# Power_Supply.net
KiCad netlist of a schematic drawn in Altium Designer
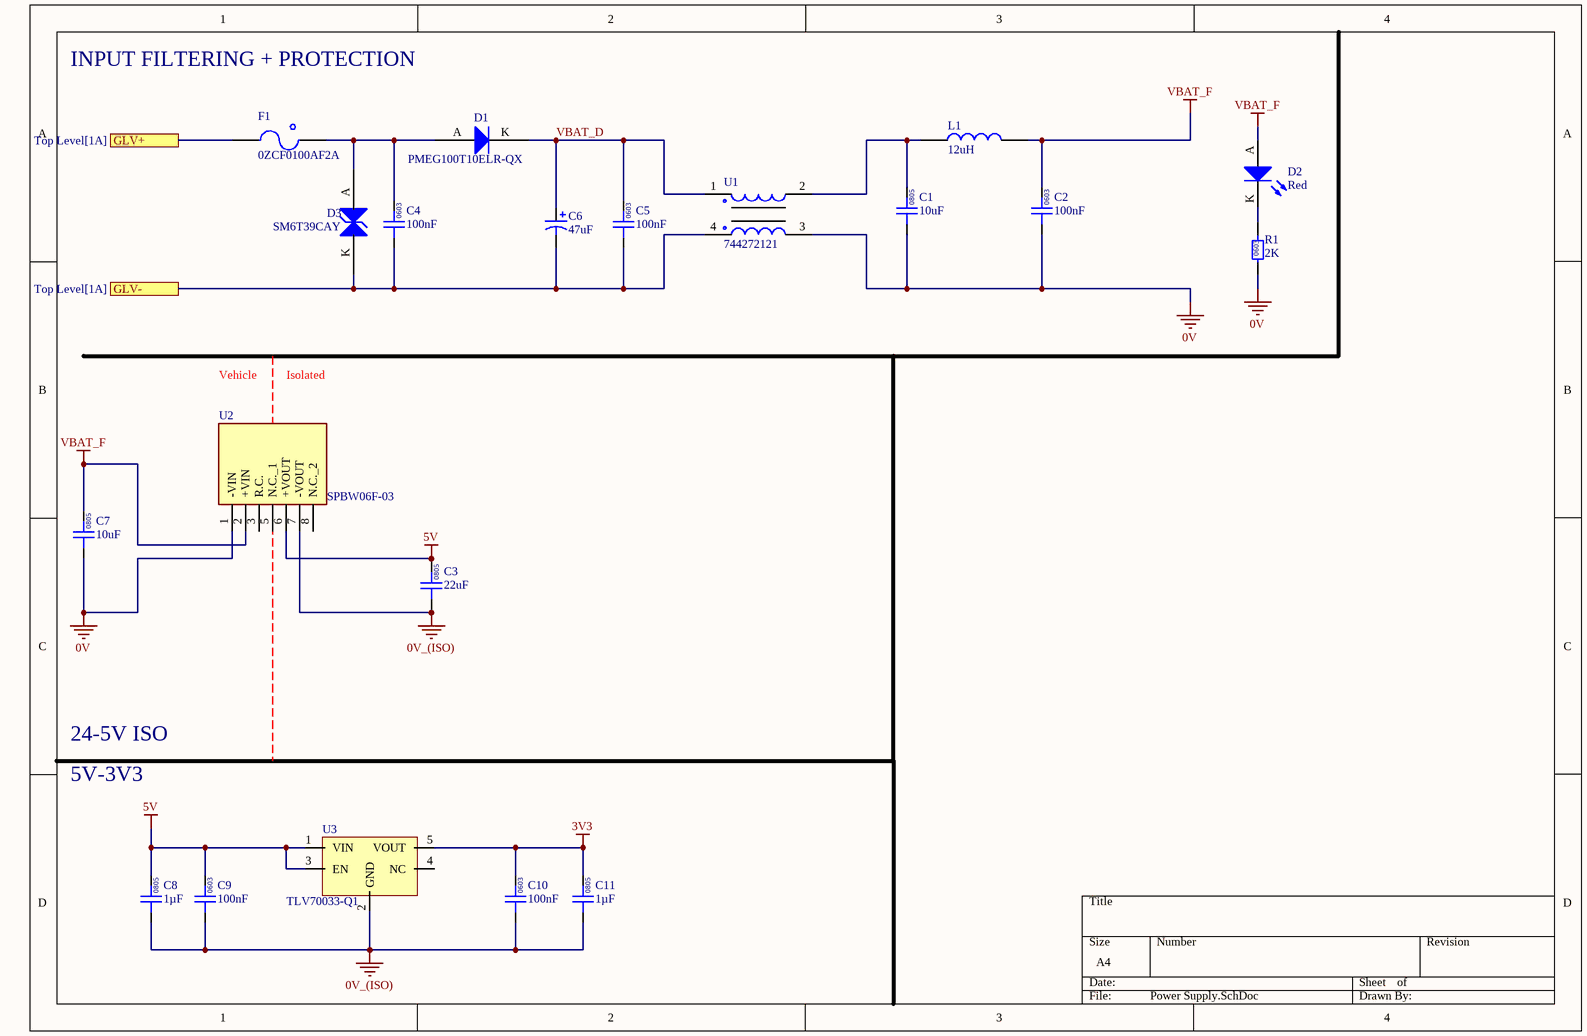
[diagram p0: Power Supply.SchDoc]

(export (version "E")
  (design (tool "Eeschema 10.0.6"))
  (components
    (comp (ref "C1")
      (value "10uF")
      (footprint "0805")
      (fields
        (field (name "PART NUMBER") "GRM21BR6YA106KE43L")
        (field (name "MANUFACTURER") "muRata")
        (field (name "TOLERANCE") "10%")
      )
      (libsource (lib "ts_standard_library") (part "Capacitor 0805"))
    )
    (comp (ref "C2")
      (value "100nF")
      (footprint "0603")
      (fields
        (field (name "PART NUMBER") "GCM188L81H104KA57D")
        (field (name "MANUFACTURER") "muRata")
        (field (name "TOLERANCE") "±10%")
      )
      (libsource (lib "ts_standard_library") (part "Capacitor 0603"))
    )
    (comp (ref "C3")
      (value "22uF")
      (footprint "0805")
      (fields
        (field (name "PART NUMBER") "GRM21BR61A226ME51L")
        (field (name "MANUFACTURER") "muRata")
        (field (name "TOLERANCE") "20%")
      )
      (libsource (lib "ts_standard_library") (part "Capacitor 0805"))
    )
    (comp (ref "C4")
      (value "100nF")
      (footprint "0603")
      (fields
        (field (name "PART NUMBER") "GCM188L81H104KA57D")
        (field (name "MANUFACTURER") "muRata")
        (field (name "TOLERANCE") "±10%")
      )
      (libsource (lib "ts_standard_library") (part "Capacitor 0603"))
    )
    (comp (ref "C5")
      (value "100nF")
      (footprint "0603")
      (fields
        (field (name "PART NUMBER") "GCM188L81H104KA57D")
        (field (name "MANUFACTURER") "muRata")
        (field (name "TOLERANCE") "±10%")
      )
      (libsource (lib "ts_standard_library") (part "Capacitor 0603"))
    )
    (comp (ref "C6")
      (value "47uF")
      (footprint "CHEMI-CON ELCO")
      (fields (field (name "PART NUMBER") "HHXA350ARA470MF61G"))
      (libsource (lib "ts_standard_library") (part "Capacitor (Polarised)"))
    )
    (comp (ref "C7")
      (value "10uF")
      (footprint "0805")
      (fields
        (field (name "PART NUMBER") "GRM21BR6YA106KE43L")
        (field (name "MANUFACTURER") "muRata")
        (field (name "TOLERANCE") "10%")
      )
      (libsource (lib "ts_standard_library") (part "Capacitor 0805"))
    )
    (comp (ref "C8")
      (value "1µF")
      (footprint "0805")
      (fields
        (field (name "PART NUMBER") "GCM21BR71H105KA03L")
        (field (name "MANUFACTURER") "muRata")
        (field (name "TOLERANCE") "±10%")
      )
      (libsource (lib "ts_standard_library") (part "Capacitor 0805"))
    )
    (comp (ref "C9")
      (value "100nF")
      (footprint "0603")
      (fields
        (field (name "PART NUMBER") "GCM188L81H104KA57D")
        (field (name "MANUFACTURER") "muRata")
        (field (name "TOLERANCE") "±10%")
      )
      (libsource (lib "ts_standard_library") (part "Capacitor 0603"))
    )
    (comp (ref "C10")
      (value "100nF")
      (footprint "0603")
      (fields
        (field (name "PART NUMBER") "GCM188L81H104KA57D")
        (field (name "MANUFACTURER") "muRata")
        (field (name "TOLERANCE") "±10%")
      )
      (libsource (lib "ts_standard_library") (part "Capacitor 0603"))
    )
    (comp (ref "C11")
      (value "1µF")
      (footprint "0805")
      (fields
        (field (name "PART NUMBER") "GCM21BR71H105KA03L")
        (field (name "MANUFACTURER") "muRata")
        (field (name "TOLERANCE") "±10%")
      )
      (libsource (lib "ts_standard_library") (part "Capacitor 0805"))
    )
    (comp (ref "D1")
      (value "PMEG100T10ELR-QX")
      (footprint "SODFL350X110-2N")
      (description "Diode 100 V 1A Surface Mount SOD-123W")
      (libsource (lib "Team Swinburne") (part "PMEG100T10ELR-QX"))
    )
    (comp (ref "D2")
      (value "Red")
      (footprint "0805 LED")
      (description "Red LED Indication - Discrete 1.75V 0805 (2012 Metric)")
      (fields (field (name "PART NUMBER") "SML-210LTT86") (field (name "MANUFACTURER") "ROHM Semiconductor"))
      (libsource (lib "ts_standard_library") (part "LED"))
    )
    (comp (ref "D3")
      (value "SM6T39CAY")
      (footprint "SM6T39CAY-Footprint-1")
      (description "TVS Diode Single Bi-Dir 33.3V 600W Automotive 2-Pin SMB T/R / TVS DIODE 33.3VWM 69.7VC SMB")
      (libsource (lib "Team Swinburne") (part "SM6T39CAY-Symbol"))
    )
    (comp (ref "F1")
      (value "0ZCF0100AF2A")
      (footprint "2920")
      (description "PTC RESET FUSE 60V 1A 292")
      (fields
        (field (name "MANUFACTURER") "Littelfuse Inc.")
        (field (name "DIGIKEY PART NUMBER") "507-2070-1-ND")
      )
      (libsource (lib "ts_standard_library") (part "PTC Fuse"))
    )
    (comp (ref "L1")
      (value "12uH")
      (footprint "1812")
      (fields
        (field (name "PART NUMBER") "RLS-126")
        (field (name "MANUFACTURER") "Recom")
        (field (name "TOLERANCE") "0.2")
      )
      (libsource (lib "ts_standard_library") (part "Inductor"))
    )
    (comp (ref "R1")
      (value "2K")
      (footprint "0603")
      (fields
        (field (name "PART NUMBER") "RC0603FR-072KL")
        (field (name "MANUFACTURER") "YAGEO")
        (field (name "TOLERANCE") "0.01")
      )
      (libsource (lib "ts_standard_library") (part "Resistor 0603"))
    )
    (comp (ref "U1")
      (value "744272121")
      (footprint "Wurth 4-PC Pad")
      (fields
        (field (name "MANUFACTURER") "Wurth Electronics Inc")
        (field (name "DIGIKEY PART NUMBER") "732-1489-1-ND")
      )
      (libsource (lib "ts_standard_library") (part "CM Choke"))
    )
    (comp (ref "U2")
      (value "SPBW06F-03")
      (footprint "SamacSys:SPBW06F03")
      (description "Power Supply")
      (fields (field (name "MOUSER PART NUMBER") "709-SPBW06F-03"))
      (libsource (lib "*") (part "SPBW06F-03"))
    )
    (comp (ref "U3")
      (value "TLV70033-Q1")
      (footprint "TI SOT-23-5")
      (description "IC REG LINEAR 3.3V 200MA SOT23-5")
      (fields
        (field (name "MANUFACTURER") "Texas Instruments")
        (field (name "DIGIKEY PART NUMBER") "296-27780-1-ND")
      )
      (libsource (lib "ts_standard_library") (part "TLV70033-Q1"))
    )
  )
  (nets
    (net (code "1") (name "/GLV+") (class "Default")
      (node (ref "F1") (pin "1") (pinfunction "1_1") (pintype "passive"))
    )
    (net (code "2") (name "/GLV-") (class "Default")
      (node (ref "C4") (pin "1") (pinfunction "1_1") (pintype "passive"))
      (node (ref "C5") (pin "1") (pinfunction "1_1") (pintype "passive"))
      (node (ref "C6") (pin "1") (pinfunction "1_1") (pintype "passive"))
      (node (ref "D3") (pin "K") (pintype "passive"))
      (node (ref "U1") (pin "4") (pinfunction "4_4") (pintype "passive"))
    )
    (net (code "3") (name "/VBAT_D") (class "Default")
      (node (ref "C5") (pin "2") (pinfunction "2_2") (pintype "passive"))
      (node (ref "C6") (pin "2") (pinfunction "2_2") (pintype "passive"))
      (node (ref "D1") (pin "K") (pintype "passive"))
      (node (ref "U1") (pin "1") (pinfunction "1_1") (pintype "passive"))
    )
    (net (code "4") (name "0V") (class "Default")
      (node (ref "C1") (pin "1") (pinfunction "1_1") (pintype "passive"))
      (node (ref "C2") (pin "1") (pinfunction "1_1") (pintype "passive"))
      (node (ref "C7") (pin "1") (pinfunction "1_1") (pintype "passive"))
      (node (ref "R1") (pin "1") (pinfunction "1_1") (pintype "passive"))
      (node (ref "U1") (pin "3") (pinfunction "3_3") (pintype "power_in"))
      (node (ref "U2") (pin "1") (pinfunction "-VIN_1") (pintype "passive"))
    )
    (net (code "5") (name "0V_(ISO)") (class "Default")
      (node (ref "C10") (pin "1") (pinfunction "1_1") (pintype "passive"))
      (node (ref "C11") (pin "1") (pinfunction "1_1") (pintype "passive"))
      (node (ref "C3") (pin "1") (pinfunction "1_1") (pintype "passive"))
      (node (ref "C8") (pin "1") (pinfunction "1_1") (pintype "passive"))
      (node (ref "C9") (pin "1") (pinfunction "1_1") (pintype "passive"))
      (node (ref "U2") (pin "7") (pinfunction "-VOUT_7") (pintype "passive"))
      (node (ref "U3") (pin "2") (pinfunction "GND_2") (pintype "passive"))
    )
    (net (code "6") (name "3V3") (class "Default")
      (node (ref "C10") (pin "2") (pinfunction "2_2") (pintype "passive"))
      (node (ref "C11") (pin "2") (pinfunction "2_2") (pintype "passive"))
      (node (ref "U3") (pin "5") (pinfunction "VOUT_5") (pintype "passive"))
    )
    (net (code "7") (name "5V") (class "Default")
      (node (ref "C3") (pin "2") (pinfunction "2_2") (pintype "passive"))
      (node (ref "C8") (pin "2") (pinfunction "2_2") (pintype "passive"))
      (node (ref "C9") (pin "2") (pinfunction "2_2") (pintype "passive"))
      (node (ref "U2") (pin "6") (pinfunction "+VOUT_6") (pintype "passive"))
      (node (ref "U3") (pin "1") (pinfunction "VIN_1") (pintype "passive"))
      (node (ref "U3") (pin "3") (pinfunction "EN_3") (pintype "passive"))
    )
    (net (code "8") (name "Net-(C1-Pad2)") (class "Default")
      (node (ref "C1") (pin "2") (pinfunction "2_2") (pintype "passive"))
      (node (ref "L1") (pin "2") (pinfunction "2_2") (pintype "passive"))
      (node (ref "U1") (pin "2") (pinfunction "2_2") (pintype "passive"))
    )
    (net (code "9") (name "Net-(C4-Pad2)") (class "Default")
      (node (ref "C4") (pin "2") (pinfunction "2_2") (pintype "passive"))
      (node (ref "D1") (pin "A") (pintype "passive"))
      (node (ref "D3") (pin "A") (pintype "passive"))
      (node (ref "F1") (pin "2") (pinfunction "2_2") (pintype "passive"))
    )
    (net (code "10") (name "Net-(D2-PadK)") (class "Default")
      (node (ref "D2") (pin "K") (pinfunction "K_K") (pintype "passive"))
      (node (ref "R1") (pin "2") (pinfunction "2_2") (pintype "passive"))
    )
    (net (code "11") (name "VBAT_F") (class "Default")
      (node (ref "C2") (pin "2") (pinfunction "2_2") (pintype "passive"))
      (node (ref "C7") (pin "2") (pinfunction "2_2") (pintype "passive"))
      (node (ref "D2") (pin "A") (pinfunction "A_A") (pintype "passive"))
      (node (ref "L1") (pin "1") (pinfunction "1_1") (pintype "passive"))
      (node (ref "U2") (pin "2") (pinfunction "+VIN_2") (pintype "passive"))
    )
    (net (code "12") (name "unconnected-(U2-N.C._1-Pad5)") (class "Default")
      (node (ref "U2") (pin "5") (pinfunction "N.C._1_5") (pintype "passive"))
    )
    (net (code "13") (name "unconnected-(U2-N.C._2-Pad8)") (class "Default")
      (node (ref "U2") (pin "8") (pinfunction "N.C._2_8") (pintype "passive"))
    )
    (net (code "14") (name "unconnected-(U2-R.C.-Pad3)") (class "Default")
      (node (ref "U2") (pin "3") (pinfunction "R.C._3") (pintype "passive"))
    )
    (net (code "15") (name "unconnected-(U3-NC-Pad4)") (class "Default")
      (node (ref "U3") (pin "4") (pinfunction "NC_4") (pintype "passive"))
    )
  )
)
